# MB_RELAY.net
KiCad netlist of a schematic drawn in Altium Designer
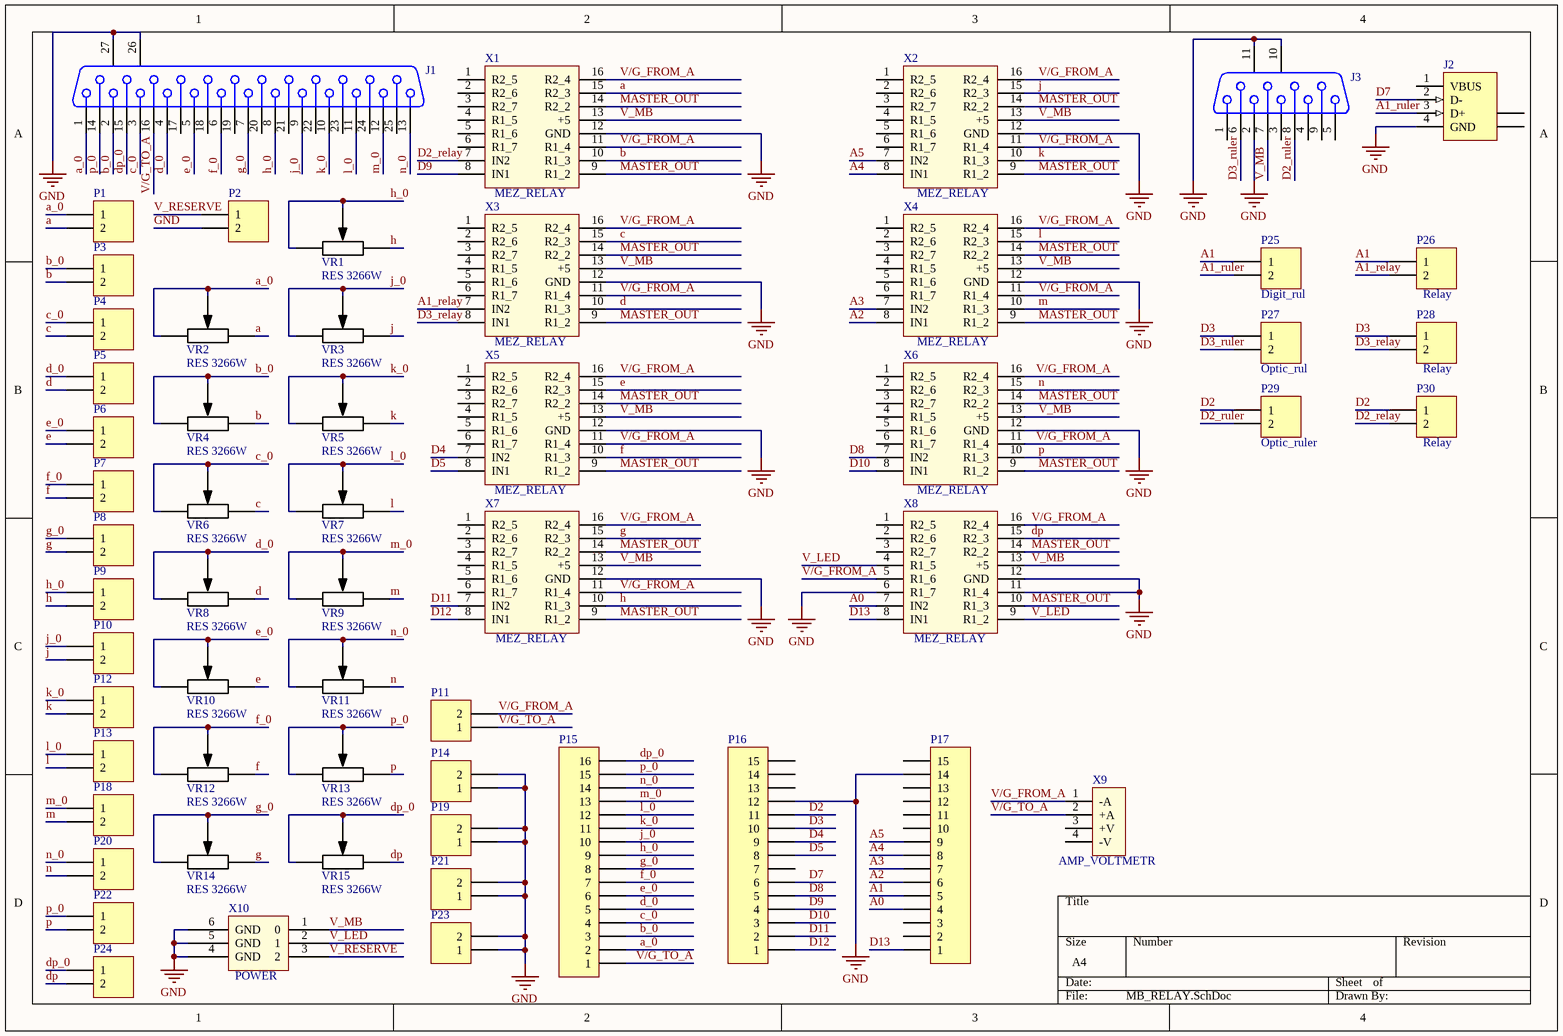
[diagram p0: MB_RELAY.SchDoc]

(export (version "E")
  (design (tool "Eeschema 10.0.6"))
  (components
    (comp (ref "J1")
      (value "D Connector 25")
      (footprint "DSUB1.385-2H25A")
      (description "Receptacle Assembly, 25 Position, Right Angle")
      (fields (field (name "PUBLISHER") "Altium Limited"))
      (libsource (lib "Miscellaneous Connectors") (part "D Connector 25"))
    )
    (comp (ref "J2")
      (value "1-353576-1")
      (footprint "353576")
      (description "USB 1.1, Right Angle, SMT, A Type, Receptacle, 4 Position, White")
      (fields (field (name "PUBLISHER") "Altium Limited"))
      (libsource (lib "AMP Serial Bus USB") (part "1-353576-1"))
    )
    (comp (ref "J3")
      (value "D Connector 9")
      (footprint "DSUB1.385-2H9")
      (description "Receptacle Assembly, 9 Position, Right Angle")
      (fields (field (name "PUBLISHER") "Altium Limited"))
      (libsource (lib "Miscellaneous Connectors") (part "D Connector 9"))
    )
    (comp (ref "P1")
      (value "Header 2")
      (footprint "HDR1X2")
      (description "Header, 2-Pin")
      (fields (field (name "PUBLISHER") "Altium Limited"))
      (libsource (lib "") (part "Header 2_1"))
    )
    (comp (ref "P2")
      (value "Header 2")
      (footprint "HDR1X2")
      (description "Header, 2-Pin")
      (fields (field (name "PUBLISHER") "Altium Limited"))
      (libsource (lib "") (part "Header 2_1"))
    )
    (comp (ref "P3")
      (value "Header 2")
      (footprint "HDR1X2")
      (description "Header, 2-Pin")
      (fields (field (name "PUBLISHER") "Altium Limited"))
      (libsource (lib "") (part "Header 2_1"))
    )
    (comp (ref "P4")
      (value "Header 2")
      (footprint "HDR1X2")
      (description "Header, 2-Pin")
      (fields (field (name "PUBLISHER") "Altium Limited"))
      (libsource (lib "") (part "Header 2_1"))
    )
    (comp (ref "P5")
      (value "Header 2")
      (footprint "HDR1X2")
      (description "Header, 2-Pin")
      (fields (field (name "PUBLISHER") "Altium Limited"))
      (libsource (lib "") (part "Header 2_1"))
    )
    (comp (ref "P6")
      (value "GND")
      (footprint "HDR1X2")
      (description "Header, 2-Pin")
      (fields (field (name "PUBLISHER") "Altium Limited"))
      (libsource (lib "") (part "Header 2_1"))
    )
    (comp (ref "P7")
      (value "GND")
      (footprint "HDR1X2")
      (description "Header, 2-Pin")
      (fields (field (name "PUBLISHER") "Altium Limited"))
      (libsource (lib "") (part "Header 2_1"))
    )
    (comp (ref "P8")
      (value "GND")
      (footprint "HDR1X2")
      (description "Header, 2-Pin")
      (fields (field (name "PUBLISHER") "Altium Limited"))
      (libsource (lib "") (part "Header 2_1"))
    )
    (comp (ref "P9")
      (value "GND")
      (footprint "HDR1X2")
      (description "Header, 2-Pin")
      (fields (field (name "PUBLISHER") "Altium Limited"))
      (libsource (lib "") (part "Header 2_1"))
    )
    (comp (ref "P10")
      (value "Header 2")
      (footprint "HDR1X2")
      (description "Header, 2-Pin")
      (fields (field (name "PUBLISHER") "Altium Limited"))
      (libsource (lib "") (part "Header 2_1"))
    )
    (comp (ref "P11")
      (value "Header 2")
      (footprint "HDR1X2")
      (description "Header, 2-Pin")
      (fields (field (name "PUBLISHER") "Altium Limited"))
      (libsource (lib "Miscellaneous Connectors") (part "Header 2"))
    )
    (comp (ref "P12")
      (value "Header 2")
      (footprint "HDR1X2")
      (description "Header, 2-Pin")
      (fields (field (name "PUBLISHER") "Altium Limited"))
      (libsource (lib "") (part "Header 2_1"))
    )
    (comp (ref "P13")
      (value "GND")
      (footprint "HDR1X2")
      (description "Header, 2-Pin")
      (fields (field (name "PUBLISHER") "Altium Limited"))
      (libsource (lib "") (part "Header 2_1"))
    )
    (comp (ref "P14")
      (value "GND")
      (footprint "HDR1X2")
      (description "Header, 2-Pin")
      (fields (field (name "PUBLISHER") "Altium Limited"))
      (libsource (lib "Miscellaneous Connectors") (part "Header 2"))
    )
    (comp (ref "P15")
      (value "Header 16")
      (footprint "HDR1X16")
      (description "Header, 16-Pin")
      (fields (field (name "PUBLISHER") "Altium Limited"))
      (libsource (lib "Miscellaneous Connectors") (part "Header 16"))
    )
    (comp (ref "P16")
      (value "Header 15")
      (footprint "HDR1X15")
      (description "Header, 15-Pin")
      (fields (field (name "PUBLISHER") "Altium Limited"))
      (libsource (lib "Miscellaneous Connectors") (part "Header 15"))
    )
    (comp (ref "P17")
      (value "Header 15")
      (footprint "HDR1X15")
      (description "Header, 15-Pin")
      (fields (field (name "PUBLISHER") "Altium Limited"))
      (libsource (lib "") (part "Header 15_1"))
    )
    (comp (ref "P18")
      (value "GND")
      (footprint "HDR1X2")
      (description "Header, 2-Pin")
      (fields (field (name "PUBLISHER") "Altium Limited"))
      (libsource (lib "") (part "Header 2_1"))
    )
    (comp (ref "P19")
      (value "GND")
      (footprint "HDR1X2")
      (description "Header, 2-Pin")
      (fields (field (name "PUBLISHER") "Altium Limited"))
      (libsource (lib "Miscellaneous Connectors") (part "Header 2"))
    )
    (comp (ref "P20")
      (value "GND")
      (footprint "HDR1X2")
      (description "Header, 2-Pin")
      (fields (field (name "PUBLISHER") "Altium Limited"))
      (libsource (lib "") (part "Header 2_1"))
    )
    (comp (ref "P21")
      (value "GND")
      (footprint "HDR1X2")
      (description "Header, 2-Pin")
      (fields (field (name "PUBLISHER") "Altium Limited"))
      (libsource (lib "Miscellaneous Connectors") (part "Header 2"))
    )
    (comp (ref "P22")
      (value "GND")
      (footprint "HDR1X2")
      (description "Header, 2-Pin")
      (fields (field (name "PUBLISHER") "Altium Limited"))
      (libsource (lib "") (part "Header 2_1"))
    )
    (comp (ref "P23")
      (value "GND")
      (footprint "HDR1X2")
      (description "Header, 2-Pin")
      (fields (field (name "PUBLISHER") "Altium Limited"))
      (libsource (lib "Miscellaneous Connectors") (part "Header 2"))
    )
    (comp (ref "P24")
      (value "GND")
      (footprint "HDR1X2")
      (description "Header, 2-Pin")
      (fields (field (name "PUBLISHER") "Altium Limited"))
      (libsource (lib "") (part "Header 2_1"))
    )
    (comp (ref "P25")
      (value "Digit_rul")
      (footprint "HDR1X2")
      (description "Header, 2-Pin")
      (fields (field (name "PUBLISHER") "Altium Limited"))
      (libsource (lib "") (part "Header 2_1"))
    )
    (comp (ref "P26")
      (value "Relay")
      (footprint "HDR1X2")
      (description "Header, 2-Pin")
      (fields (field (name "PUBLISHER") "Altium Limited"))
      (libsource (lib "") (part "Header 2_1"))
    )
    (comp (ref "P27")
      (value "Optic_rul")
      (footprint "HDR1X2")
      (description "Header, 2-Pin")
      (fields (field (name "PUBLISHER") "Altium Limited"))
      (libsource (lib "") (part "Header 2_1"))
    )
    (comp (ref "P28")
      (value "Relay")
      (footprint "HDR1X2")
      (description "Header, 2-Pin")
      (fields (field (name "PUBLISHER") "Altium Limited"))
      (libsource (lib "") (part "Header 2_1"))
    )
    (comp (ref "P29")
      (value "Optic_ruler")
      (footprint "HDR1X2")
      (description "Header, 2-Pin")
      (fields (field (name "PUBLISHER") "Altium Limited"))
      (libsource (lib "") (part "Header 2_1"))
    )
    (comp (ref "P30")
      (value "Relay")
      (footprint "HDR1X2")
      (description "Header, 2-Pin")
      (fields (field (name "PUBLISHER") "Altium Limited"))
      (libsource (lib "") (part "Header 2_1"))
    )
    (comp (ref "VR1")
      (value "RES 3266W")
      (footprint "aab_Passive:RES 3266W")
      (libsource (lib "aab_Schlib") (part "RES 3266W"))
    )
    (comp (ref "VR2")
      (value "RES 3266W")
      (footprint "aab_Passive:RES 3266W")
      (libsource (lib "aab_Schlib") (part "RES 3266W"))
    )
    (comp (ref "VR3")
      (value "RES 3266W")
      (footprint "aab_Passive:RES 3266W")
      (libsource (lib "aab_Schlib") (part "RES 3266W"))
    )
    (comp (ref "VR4")
      (value "RES 3266W")
      (footprint "aab_Passive:RES 3266W")
      (libsource (lib "aab_Schlib") (part "RES 3266W"))
    )
    (comp (ref "VR5")
      (value "RES 3266W")
      (footprint "aab_Passive:RES 3266W")
      (libsource (lib "aab_Schlib") (part "RES 3266W"))
    )
    (comp (ref "VR6")
      (value "RES 3266W")
      (footprint "aab_Passive:RES 3266W")
      (libsource (lib "aab_Schlib") (part "RES 3266W"))
    )
    (comp (ref "VR7")
      (value "RES 3266W")
      (footprint "aab_Passive:RES 3266W")
      (libsource (lib "aab_Schlib") (part "RES 3266W"))
    )
    (comp (ref "VR8")
      (value "RES 3266W")
      (footprint "aab_Passive:RES 3266W")
      (libsource (lib "aab_Schlib") (part "RES 3266W"))
    )
    (comp (ref "VR9")
      (value "RES 3266W")
      (footprint "aab_Passive:RES 3266W")
      (libsource (lib "aab_Schlib") (part "RES 3266W"))
    )
    (comp (ref "VR10")
      (value "RES 3266W")
      (footprint "aab_Passive:RES 3266W")
      (libsource (lib "aab_Schlib") (part "RES 3266W"))
    )
    (comp (ref "VR11")
      (value "RES 3266W")
      (footprint "aab_Passive:RES 3266W")
      (libsource (lib "aab_Schlib") (part "RES 3266W"))
    )
    (comp (ref "VR12")
      (value "RES 3266W")
      (footprint "aab_Passive:RES 3266W")
      (libsource (lib "aab_Schlib") (part "RES 3266W"))
    )
    (comp (ref "VR13")
      (value "RES 3266W")
      (footprint "aab_Passive:RES 3266W")
      (libsource (lib "aab_Schlib") (part "RES 3266W"))
    )
    (comp (ref "VR14")
      (value "RES 3266W")
      (footprint "aab_Passive:RES 3266W")
      (libsource (lib "aab_Schlib") (part "RES 3266W"))
    )
    (comp (ref "VR15")
      (value "RES 3266W")
      (footprint "aab_Passive:RES 3266W")
      (libsource (lib "aab_Schlib") (part "RES 3266W"))
    )
    (comp (ref "X1")
      (value "MEZ_RELAY")
      (footprint "MEZ_RELAY")
      (libsource (lib "msp_SchLib") (part "MEZ_RELAY"))
    )
    (comp (ref "X2")
      (value "MEZ_RELAY")
      (footprint "MEZ_RELAY")
      (libsource (lib "msp_SchLib") (part "MEZ_RELAY"))
    )
    (comp (ref "X3")
      (value "MEZ_RELAY")
      (footprint "MEZ_RELAY")
      (libsource (lib "msp_SchLib") (part "MEZ_RELAY"))
    )
    (comp (ref "X4")
      (value "MEZ_RELAY")
      (footprint "MEZ_RELAY")
      (libsource (lib "msp_SchLib") (part "MEZ_RELAY"))
    )
    (comp (ref "X5")
      (value "MEZ_RELAY")
      (footprint "MEZ_RELAY")
      (libsource (lib "msp_SchLib") (part "MEZ_RELAY"))
    )
    (comp (ref "X6")
      (value "MEZ_RELAY")
      (footprint "MEZ_RELAY")
      (libsource (lib "msp_SchLib") (part "MEZ_RELAY"))
    )
    (comp (ref "X7")
      (value "MEZ_RELAY")
      (footprint "MEZ_RELAY")
      (libsource (lib "msp_SchLib") (part "MEZ_RELAY"))
    )
    (comp (ref "X8")
      (value "MEZ_RELAY")
      (footprint "MEZ_RELAY")
      (libsource (lib "msp_SchLib") (part "MEZ_RELAY"))
    )
    (comp (ref "X9")
      (value "AMP_VOLTMETR")
      (footprint "vpl_Passive:AMP_VOLTMETER")
      (libsource (lib "msp_SchLib") (part "AMP_VOLTMETR"))
    )
    (comp (ref "X10")
      (value "POWER")
      (footprint "vpl_Passive:POWER")
      (libsource (lib "msp_SchLib") (part "POWER"))
    )
  )
  (nets
    (net (code "1") (name "/A0") (class "Default")
      (node (ref "P17") (pin "4") (pinfunction "4_4") (pintype "passive"))
      (node (ref "X8") (pin "7") (pinfunction "IN2_7") (pintype "passive"))
    )
    (net (code "2") (name "/A1") (class "Default")
      (node (ref "P17") (pin "5") (pinfunction "5_5") (pintype "passive"))
      (node (ref "P25") (pin "1") (pinfunction "1_1") (pintype "passive"))
      (node (ref "P26") (pin "1") (pinfunction "1_1") (pintype "passive"))
    )
    (net (code "3") (name "/A1_relay") (class "Default")
      (node (ref "P26") (pin "2") (pinfunction "2_2") (pintype "passive"))
      (node (ref "X3") (pin "7") (pinfunction "IN2_7") (pintype "passive"))
    )
    (net (code "4") (name "/A1_ruler") (class "Default")
      (node (ref "J2") (pin "3") (pinfunction "D+_3") (pintype "input"))
      (node (ref "P25") (pin "2") (pinfunction "2_2") (pintype "passive"))
    )
    (net (code "5") (name "/A2") (class "Default")
      (node (ref "P17") (pin "6") (pinfunction "6_6") (pintype "passive"))
      (node (ref "X4") (pin "8") (pinfunction "IN1_8") (pintype "passive"))
    )
    (net (code "6") (name "/A3") (class "Default")
      (node (ref "P17") (pin "7") (pinfunction "7_7") (pintype "passive"))
      (node (ref "X4") (pin "7") (pinfunction "IN2_7") (pintype "passive"))
    )
    (net (code "7") (name "/A4") (class "Default")
      (node (ref "P17") (pin "8") (pinfunction "8_8") (pintype "passive"))
      (node (ref "X2") (pin "8") (pinfunction "IN1_8") (pintype "passive"))
    )
    (net (code "8") (name "/A5") (class "Default")
      (node (ref "P17") (pin "9") (pinfunction "9_9") (pintype "passive"))
      (node (ref "X2") (pin "7") (pinfunction "IN2_7") (pintype "passive"))
    )
    (net (code "9") (name "/D2") (class "Default")
      (node (ref "P16") (pin "11") (pinfunction "11_11") (pintype "passive"))
      (node (ref "P29") (pin "1") (pinfunction "1_1") (pintype "passive"))
      (node (ref "P30") (pin "1") (pinfunction "1_1") (pintype "passive"))
    )
    (net (code "10") (name "/D2_relay") (class "Default")
      (node (ref "P30") (pin "2") (pinfunction "2_2") (pintype "passive"))
      (node (ref "X1") (pin "7") (pinfunction "IN2_7") (pintype "passive"))
    )
    (net (code "11") (name "/D2_ruler") (class "Default")
      (node (ref "J3") (pin "8") (pinfunction "8_8") (pintype "passive"))
      (node (ref "P29") (pin "2") (pinfunction "2_2") (pintype "passive"))
    )
    (net (code "12") (name "/D3") (class "Default")
      (node (ref "P16") (pin "10") (pinfunction "10_10") (pintype "passive"))
      (node (ref "P27") (pin "1") (pinfunction "1_1") (pintype "passive"))
      (node (ref "P28") (pin "1") (pinfunction "1_1") (pintype "passive"))
    )
    (net (code "13") (name "/D3_relay") (class "Default")
      (node (ref "P28") (pin "2") (pinfunction "2_2") (pintype "passive"))
      (node (ref "X3") (pin "8") (pinfunction "IN1_8") (pintype "passive"))
    )
    (net (code "14") (name "/D3_ruler") (class "Default")
      (node (ref "J3") (pin "6") (pinfunction "6_6") (pintype "passive"))
      (node (ref "P27") (pin "2") (pinfunction "2_2") (pintype "passive"))
    )
    (net (code "15") (name "/D4") (class "Default")
      (node (ref "P16") (pin "9") (pinfunction "9_9") (pintype "passive"))
      (node (ref "X5") (pin "7") (pinfunction "IN2_7") (pintype "passive"))
    )
    (net (code "16") (name "/D5") (class "Default")
      (node (ref "P16") (pin "8") (pinfunction "8_8") (pintype "passive"))
      (node (ref "X5") (pin "8") (pinfunction "IN1_8") (pintype "passive"))
    )
    (net (code "17") (name "/D7") (class "Default")
      (node (ref "J2") (pin "2") (pinfunction "D-_2") (pintype "input"))
      (node (ref "P16") (pin "6") (pinfunction "6_6") (pintype "passive"))
    )
    (net (code "18") (name "/D8") (class "Default")
      (node (ref "P16") (pin "5") (pinfunction "5_5") (pintype "passive"))
      (node (ref "X6") (pin "7") (pinfunction "IN2_7") (pintype "passive"))
    )
    (net (code "19") (name "/D9") (class "Default")
      (node (ref "P16") (pin "4") (pinfunction "4_4") (pintype "passive"))
      (node (ref "X1") (pin "8") (pinfunction "IN1_8") (pintype "passive"))
    )
    (net (code "20") (name "/D10") (class "Default")
      (node (ref "P16") (pin "3") (pinfunction "3_3") (pintype "passive"))
      (node (ref "X6") (pin "8") (pinfunction "IN1_8") (pintype "passive"))
    )
    (net (code "21") (name "/D11") (class "Default")
      (node (ref "P16") (pin "2") (pinfunction "2_2") (pintype "passive"))
      (node (ref "X7") (pin "7") (pinfunction "IN2_7") (pintype "passive"))
    )
    (net (code "22") (name "/D12") (class "Default")
      (node (ref "P16") (pin "1") (pinfunction "1_1") (pintype "passive"))
      (node (ref "X7") (pin "8") (pinfunction "IN1_8") (pintype "passive"))
    )
    (net (code "23") (name "/D13") (class "Default")
      (node (ref "P17") (pin "1") (pinfunction "1_1") (pintype "passive"))
      (node (ref "X8") (pin "8") (pinfunction "IN1_8") (pintype "passive"))
    )
    (net (code "24") (name "/MASTER_OUT") (class "Default")
      (node (ref "X1") (pin "14") (pinfunction "R2_2_14") (pintype "passive"))
      (node (ref "X1") (pin "9") (pinfunction "R1_2_9") (pintype "passive"))
      (node (ref "X2") (pin "14") (pinfunction "R2_2_14") (pintype "passive"))
      (node (ref "X2") (pin "9") (pinfunction "R1_2_9") (pintype "passive"))
      (node (ref "X3") (pin "14") (pinfunction "R2_2_14") (pintype "passive"))
      (node (ref "X3") (pin "9") (pinfunction "R1_2_9") (pintype "passive"))
      (node (ref "X4") (pin "14") (pinfunction "R2_2_14") (pintype "passive"))
      (node (ref "X4") (pin "9") (pinfunction "R1_2_9") (pintype "passive"))
      (node (ref "X5") (pin "14") (pinfunction "R2_2_14") (pintype "passive"))
      (node (ref "X5") (pin "9") (pinfunction "R1_2_9") (pintype "passive"))
      (node (ref "X6") (pin "14") (pinfunction "R2_2_14") (pintype "passive"))
      (node (ref "X6") (pin "9") (pinfunction "R1_2_9") (pintype "passive"))
      (node (ref "X7") (pin "14") (pinfunction "R2_2_14") (pintype "passive"))
      (node (ref "X7") (pin "9") (pinfunction "R1_2_9") (pintype "passive"))
      (node (ref "X8") (pin "10") (pinfunction "R1_3_10") (pintype "passive"))
      (node (ref "X8") (pin "14") (pinfunction "R2_2_14") (pintype "passive"))
    )
    (net (code "25") (name "/V_LED") (class "Default")
      (node (ref "X10") (pin "2") (pinfunction "1_2") (pintype "passive"))
      (node (ref "X8") (pin "4") (pinfunction "R1_5_4") (pintype "passive"))
      (node (ref "X8") (pin "9") (pinfunction "R1_2_9") (pintype "passive"))
    )
    (net (code "26") (name "/V_MB") (class "Default")
      (node (ref "J3") (pin "7") (pinfunction "7_7") (pintype "passive"))
      (node (ref "X1") (pin "13") (pinfunction "+5_13") (pintype "passive"))
      (node (ref "X10") (pin "1") (pinfunction "0_1") (pintype "passive"))
      (node (ref "X2") (pin "13") (pinfunction "+5_13") (pintype "passive"))
      (node (ref "X3") (pin "13") (pinfunction "+5_13") (pintype "passive"))
      (node (ref "X4") (pin "13") (pinfunction "+5_13") (pintype "passive"))
      (node (ref "X5") (pin "13") (pinfunction "+5_13") (pintype "passive"))
      (node (ref "X6") (pin "13") (pinfunction "+5_13") (pintype "passive"))
      (node (ref "X7") (pin "13") (pinfunction "+5_13") (pintype "passive"))
      (node (ref "X8") (pin "13") (pinfunction "+5_13") (pintype "passive"))
    )
    (net (code "27") (name "/V_RESERVE") (class "Default")
      (node (ref "P2") (pin "1") (pinfunction "1_1") (pintype "passive"))
      (node (ref "X10") (pin "3") (pinfunction "2_3") (pintype "passive"))
    )
    (net (code "28") (name "/V{slash}G_FROM_A") (class "Default")
      (node (ref "P11") (pin "2") (pinfunction "2_2") (pintype "passive"))
      (node (ref "X1") (pin "11") (pinfunction "R1_4_11") (pintype "passive"))
      (node (ref "X1") (pin "16") (pinfunction "R2_4_16") (pintype "passive"))
      (node (ref "X2") (pin "11") (pinfunction "R1_4_11") (pintype "passive"))
      (node (ref "X2") (pin "16") (pinfunction "R2_4_16") (pintype "passive"))
      (node (ref "X3") (pin "11") (pinfunction "R1_4_11") (pintype "passive"))
      (node (ref "X3") (pin "16") (pinfunction "R2_4_16") (pintype "passive"))
      (node (ref "X4") (pin "11") (pinfunction "R1_4_11") (pintype "passive"))
      (node (ref "X4") (pin "16") (pinfunction "R2_4_16") (pintype "passive"))
      (node (ref "X5") (pin "11") (pinfunction "R1_4_11") (pintype "passive"))
      (node (ref "X5") (pin "16") (pinfunction "R2_4_16") (pintype "passive"))
      (node (ref "X6") (pin "11") (pinfunction "R1_4_11") (pintype "passive"))
      (node (ref "X6") (pin "16") (pinfunction "R2_4_16") (pintype "passive"))
      (node (ref "X7") (pin "11") (pinfunction "R1_4_11") (pintype "passive"))
      (node (ref "X7") (pin "16") (pinfunction "R2_4_16") (pintype "passive"))
      (node (ref "X8") (pin "16") (pinfunction "R2_4_16") (pintype "passive"))
      (node (ref "X8") (pin "5") (pinfunction "R1_6_5") (pintype "passive"))
      (node (ref "X9") (pin "1") (pinfunction "-A_1") (pintype "passive"))
    )
    (net (code "29") (name "/V{slash}G_TO_A") (class "Default")
      (node (ref "J1") (pin "16") (pinfunction "16_16") (pintype "passive"))
      (node (ref "P11") (pin "1") (pinfunction "1_1") (pintype "passive"))
      (node (ref "P15") (pin "1") (pinfunction "1_1") (pintype "passive"))
      (node (ref "X9") (pin "2") (pinfunction "+A_2") (pintype "passive"))
    )
    (net (code "30") (name "/a") (class "Default")
      (node (ref "P1") (pin "2") (pinfunction "2_2") (pintype "passive"))
      (node (ref "VR2") (pin "3") (pinfunction "3_3") (pintype "passive"))
      (node (ref "X1") (pin "15") (pinfunction "R2_3_15") (pintype "passive"))
    )
    (net (code "31") (name "/a_0") (class "Default")
      (node (ref "J1") (pin "1") (pinfunction "1_1") (pintype "passive"))
      (node (ref "P1") (pin "1") (pinfunction "1_1") (pintype "passive"))
      (node (ref "P15") (pin "2") (pinfunction "2_2") (pintype "passive"))
      (node (ref "VR2") (pin "1") (pinfunction "1_1") (pintype "passive"))
      (node (ref "VR2") (pin "2") (pinfunction "2_2") (pintype "passive"))
    )
    (net (code "32") (name "/b") (class "Default")
      (node (ref "P3") (pin "2") (pinfunction "2_2") (pintype "passive"))
      (node (ref "VR4") (pin "3") (pinfunction "3_3") (pintype "passive"))
      (node (ref "X1") (pin "10") (pinfunction "R1_3_10") (pintype "passive"))
    )
    (net (code "33") (name "/b_0") (class "Default")
      (node (ref "J1") (pin "2") (pinfunction "2_2") (pintype "passive"))
      (node (ref "P15") (pin "3") (pinfunction "3_3") (pintype "passive"))
      (node (ref "P3") (pin "1") (pinfunction "1_1") (pintype "passive"))
      (node (ref "VR4") (pin "1") (pinfunction "1_1") (pintype "passive"))
      (node (ref "VR4") (pin "2") (pinfunction "2_2") (pintype "passive"))
    )
    (net (code "34") (name "/c") (class "Default")
      (node (ref "P4") (pin "2") (pinfunction "2_2") (pintype "passive"))
      (node (ref "VR6") (pin "3") (pinfunction "3_3") (pintype "passive"))
      (node (ref "X3") (pin "15") (pinfunction "R2_3_15") (pintype "passive"))
    )
    (net (code "35") (name "/c_0") (class "Default")
      (node (ref "J1") (pin "3") (pinfunction "3_3") (pintype "passive"))
      (node (ref "P15") (pin "4") (pinfunction "4_4") (pintype "passive"))
      (node (ref "P4") (pin "1") (pinfunction "1_1") (pintype "passive"))
      (node (ref "VR6") (pin "1") (pinfunction "1_1") (pintype "passive"))
      (node (ref "VR6") (pin "2") (pinfunction "2_2") (pintype "passive"))
    )
    (net (code "36") (name "/d") (class "Default")
      (node (ref "P5") (pin "2") (pinfunction "2_2") (pintype "passive"))
      (node (ref "VR8") (pin "3") (pinfunction "3_3") (pintype "passive"))
      (node (ref "X3") (pin "10") (pinfunction "R1_3_10") (pintype "passive"))
    )
    (net (code "37") (name "/d_0") (class "Default")
      (node (ref "J1") (pin "4") (pinfunction "4_4") (pintype "passive"))
      (node (ref "P15") (pin "5") (pinfunction "5_5") (pintype "passive"))
      (node (ref "P5") (pin "1") (pinfunction "1_1") (pintype "passive"))
      (node (ref "VR8") (pin "1") (pinfunction "1_1") (pintype "passive"))
      (node (ref "VR8") (pin "2") (pinfunction "2_2") (pintype "passive"))
    )
    (net (code "38") (name "/dp") (class "Default")
      (node (ref "P24") (pin "2") (pinfunction "2_2") (pintype "passive"))
      (node (ref "VR15") (pin "3") (pinfunction "3_3") (pintype "passive"))
      (node (ref "X8") (pin "15") (pinfunction "R2_3_15") (pintype "passive"))
    )
    (net (code "39") (name "/dp_0") (class "Default")
      (node (ref "J1") (pin "15") (pinfunction "15_15") (pintype "passive"))
      (node (ref "P15") (pin "16") (pinfunction "16_16") (pintype "passive"))
      (node (ref "P24") (pin "1") (pinfunction "1_1") (pintype "passive"))
      (node (ref "VR15") (pin "1") (pinfunction "1_1") (pintype "passive"))
      (node (ref "VR15") (pin "2") (pinfunction "2_2") (pintype "passive"))
    )
    (net (code "40") (name "/e") (class "Default")
      (node (ref "P6") (pin "2") (pinfunction "2_2") (pintype "passive"))
      (node (ref "VR10") (pin "3") (pinfunction "3_3") (pintype "passive"))
      (node (ref "X5") (pin "15") (pinfunction "R2_3_15") (pintype "passive"))
    )
    (net (code "41") (name "/e_0") (class "Default")
      (node (ref "J1") (pin "5") (pinfunction "5_5") (pintype "passive"))
      (node (ref "P15") (pin "6") (pinfunction "6_6") (pintype "passive"))
      (node (ref "P6") (pin "1") (pinfunction "1_1") (pintype "passive"))
      (node (ref "VR10") (pin "1") (pinfunction "1_1") (pintype "passive"))
      (node (ref "VR10") (pin "2") (pinfunction "2_2") (pintype "passive"))
    )
    (net (code "42") (name "/f") (class "Default")
      (node (ref "P7") (pin "2") (pinfunction "2_2") (pintype "passive"))
      (node (ref "VR12") (pin "3") (pinfunction "3_3") (pintype "passive"))
      (node (ref "X5") (pin "10") (pinfunction "R1_3_10") (pintype "passive"))
    )
    (net (code "43") (name "/f_0") (class "Default")
      (node (ref "J1") (pin "6") (pinfunction "6_6") (pintype "passive"))
      (node (ref "P15") (pin "7") (pinfunction "7_7") (pintype "passive"))
      (node (ref "P7") (pin "1") (pinfunction "1_1") (pintype "passive"))
      (node (ref "VR12") (pin "1") (pinfunction "1_1") (pintype "passive"))
      (node (ref "VR12") (pin "2") (pinfunction "2_2") (pintype "passive"))
    )
    (net (code "44") (name "/g") (class "Default")
      (node (ref "P8") (pin "2") (pinfunction "2_2") (pintype "passive"))
      (node (ref "VR14") (pin "3") (pinfunction "3_3") (pintype "passive"))
      (node (ref "X7") (pin "15") (pinfunction "R2_3_15") (pintype "passive"))
    )
    (net (code "45") (name "/g_0") (class "Default")
      (node (ref "J1") (pin "7") (pinfunction "7_7") (pintype "passive"))
      (node (ref "P15") (pin "8") (pinfunction "8_8") (pintype "passive"))
      (node (ref "P8") (pin "1") (pinfunction "1_1") (pintype "passive"))
      (node (ref "VR14") (pin "1") (pinfunction "1_1") (pintype "passive"))
      (node (ref "VR14") (pin "2") (pinfunction "2_2") (pintype "passive"))
    )
    (net (code "46") (name "/h") (class "Default")
      (node (ref "P9") (pin "2") (pinfunction "2_2") (pintype "passive"))
      (node (ref "VR1") (pin "3") (pinfunction "3_3") (pintype "passive"))
      (node (ref "X7") (pin "10") (pinfunction "R1_3_10") (pintype "passive"))
    )
    (net (code "47") (name "/h_0") (class "Default")
      (node (ref "J1") (pin "8") (pinfunction "8_8") (pintype "passive"))
      (node (ref "P15") (pin "9") (pinfunction "9_9") (pintype "passive"))
      (node (ref "P9") (pin "1") (pinfunction "1_1") (pintype "passive"))
      (node (ref "VR1") (pin "1") (pinfunction "1_1") (pintype "passive"))
      (node (ref "VR1") (pin "2") (pinfunction "2_2") (pintype "passive"))
    )
    (net (code "48") (name "/j") (class "Default")
      (node (ref "P10") (pin "2") (pinfunction "2_2") (pintype "passive"))
      (node (ref "VR3") (pin "3") (pinfunction "3_3") (pintype "passive"))
      (node (ref "X2") (pin "15") (pinfunction "R2_3_15") (pintype "passive"))
    )
    (net (code "49") (name "/j_0") (class "Default")
      (node (ref "J1") (pin "9") (pinfunction "9_9") (pintype "passive"))
      (node (ref "P10") (pin "1") (pinfunction "1_1") (pintype "passive"))
      (node (ref "P15") (pin "10") (pinfunction "10_10") (pintype "passive"))
      (node (ref "VR3") (pin "1") (pinfunction "1_1") (pintype "passive"))
      (node (ref "VR3") (pin "2") (pinfunction "2_2") (pintype "passive"))
    )
    (net (code "50") (name "/k") (class "Default")
      (node (ref "P12") (pin "2") (pinfunction "2_2") (pintype "passive"))
      (node (ref "VR5") (pin "3") (pinfunction "3_3") (pintype "passive"))
      (node (ref "X2") (pin "10") (pinfunction "R1_3_10") (pintype "passive"))
    )
    (net (code "51") (name "/k_0") (class "Default")
      (node (ref "J1") (pin "10") (pinfunction "10_10") (pintype "passive"))
      (node (ref "P12") (pin "1") (pinfunction "1_1") (pintype "passive"))
      (node (ref "P15") (pin "11") (pinfunction "11_11") (pintype "passive"))
      (node (ref "VR5") (pin "1") (pinfunction "1_1") (pintype "passive"))
      (node (ref "VR5") (pin "2") (pinfunction "2_2") (pintype "passive"))
    )
    (net (code "52") (name "/l") (class "Default")
      (node (ref "P13") (pin "2") (pinfunction "2_2") (pintype "passive"))
      (node (ref "VR7") (pin "3") (pinfunction "3_3") (pintype "passive"))
      (node (ref "X4") (pin "15") (pinfunction "R2_3_15") (pintype "passive"))
    )
    (net (code "53") (name "/l_0") (class "Default")
      (node (ref "J1") (pin "11") (pinfunction "11_11") (pintype "passive"))
      (node (ref "P13") (pin "1") (pinfunction "1_1") (pintype "passive"))
      (node (ref "P15") (pin "12") (pinfunction "12_12") (pintype "passive"))
      (node (ref "VR7") (pin "1") (pinfunction "1_1") (pintype "passive"))
      (node (ref "VR7") (pin "2") (pinfunction "2_2") (pintype "passive"))
    )
    (net (code "54") (name "/m") (class "Default")
      (node (ref "P18") (pin "2") (pinfunction "2_2") (pintype "passive"))
      (node (ref "VR9") (pin "3") (pinfunction "3_3") (pintype "passive"))
      (node (ref "X4") (pin "10") (pinfunction "R1_3_10") (pintype "passive"))
    )
    (net (code "55") (name "/m_0") (class "Default")
      (node (ref "J1") (pin "12") (pinfunction "12_12") (pintype "passive"))
      (node (ref "P15") (pin "13") (pinfunction "13_13") (pintype "passive"))
      (node (ref "P18") (pin "1") (pinfunction "1_1") (pintype "passive"))
      (node (ref "VR9") (pin "1") (pinfunction "1_1") (pintype "passive"))
      (node (ref "VR9") (pin "2") (pinfunction "2_2") (pintype "passive"))
    )
    (net (code "56") (name "/n") (class "Default")
      (node (ref "P20") (pin "2") (pinfunction "2_2") (pintype "passive"))
      (node (ref "VR11") (pin "3") (pinfunction "3_3") (pintype "passive"))
      (node (ref "X6") (pin "15") (pinfunction "R2_3_15") (pintype "passive"))
    )
    (net (code "57") (name "/n_0") (class "Default")
      (node (ref "J1") (pin "13") (pinfunction "13_13") (pintype "passive"))
      (node (ref "P15") (pin "14") (pinfunction "14_14") (pintype "passive"))
      (node (ref "P20") (pin "1") (pinfunction "1_1") (pintype "passive"))
      (node (ref "VR11") (pin "1") (pinfunction "1_1") (pintype "passive"))
      (node (ref "VR11") (pin "2") (pinfunction "2_2") (pintype "passive"))
    )
    (net (code "58") (name "/p") (class "Default")
      (node (ref "P22") (pin "2") (pinfunction "2_2") (pintype "passive"))
      (node (ref "VR13") (pin "3") (pinfunction "3_3") (pintype "passive"))
      (node (ref "X6") (pin "10") (pinfunction "R1_3_10") (pintype "passive"))
    )
    (net (code "59") (name "/p_0") (class "Default")
      (node (ref "J1") (pin "14") (pinfunction "14_14") (pintype "passive"))
      (node (ref "P15") (pin "15") (pinfunction "15_15") (pintype "passive"))
      (node (ref "P22") (pin "1") (pinfunction "1_1") (pintype "passive"))
      (node (ref "VR13") (pin "1") (pinfunction "1_1") (pintype "passive"))
      (node (ref "VR13") (pin "2") (pinfunction "2_2") (pintype "passive"))
    )
    (net (code "60") (name "GND") (class "Default")
      (node (ref "J1") (pin "26") (pinfunction "MH1_26") (pintype "passive"))
      (node (ref "J1") (pin "27") (pinfunction "MH2_27") (pintype "passive"))
      (node (ref "J2") (pin "4") (pinfunction "GND_4") (pintype "power_in"))
      (node (ref "J3") (pin "10") (pinfunction "MH1_10") (pintype "passive"))
      (node (ref "J3") (pin "11") (pinfunction "MH2_11") (pintype "passive"))
      (node (ref "J3") (pin "2") (pinfunction "2_2") (pintype "passive"))
      (node (ref "P14") (pin "1") (pinfunction "1_1") (pintype "passive"))
      (node (ref "P14") (pin "2") (pinfunction "2_2") (pintype "passive"))
      (node (ref "P16") (pin "12") (pinfunction "12_12") (pintype "passive"))
      (node (ref "P17") (pin "14") (pinfunction "14_14") (pintype "passive"))
      (node (ref "P19") (pin "1") (pinfunction "1_1") (pintype "passive"))
      (node (ref "P19") (pin "2") (pinfunction "2_2") (pintype "passive"))
      (node (ref "P2") (pin "2") (pinfunction "2_2") (pintype "passive"))
      (node (ref "P21") (pin "1") (pinfunction "1_1") (pintype "passive"))
      (node (ref "P21") (pin "2") (pinfunction "2_2") (pintype "passive"))
      (node (ref "P23") (pin "1") (pinfunction "1_1") (pintype "passive"))
      (node (ref "P23") (pin "2") (pinfunction "2_2") (pintype "passive"))
      (node (ref "X1") (pin "12") (pinfunction "GND_12") (pintype "passive"))
      (node (ref "X10") (pin "4") (pinfunction "GND_4") (pintype "passive"))
      (node (ref "X10") (pin "5") (pinfunction "GND_5") (pintype "passive"))
      (node (ref "X10") (pin "6") (pinfunction "GND_6") (pintype "passive"))
      (node (ref "X2") (pin "12") (pinfunction "GND_12") (pintype "passive"))
      (node (ref "X3") (pin "12") (pinfunction "GND_12") (pintype "passive"))
      (node (ref "X4") (pin "12") (pinfunction "GND_12") (pintype "passive"))
      (node (ref "X5") (pin "12") (pinfunction "GND_12") (pintype "passive"))
      (node (ref "X6") (pin "12") (pinfunction "GND_12") (pintype "passive"))
      (node (ref "X7") (pin "12") (pinfunction "GND_12") (pintype "passive"))
      (node (ref "X8") (pin "11") (pinfunction "R1_4_11") (pintype "passive"))
      (node (ref "X8") (pin "12") (pinfunction "GND_12") (pintype "passive"))
      (node (ref "X8") (pin "6") (pinfunction "R1_7_6") (pintype "passive"))
    )
    (net (code "61") (name "unconnected-(J1-Pad17)") (class "Default")
      (node (ref "J1") (pin "17") (pinfunction "17_17") (pintype "passive"))
    )
    (net (code "62") (name "unconnected-(J1-Pad18)") (class "Default")
      (node (ref "J1") (pin "18") (pinfunction "18_18") (pintype "passive"))
    )
    (net (code "63") (name "unconnected-(J1-Pad19)") (class "Default")
      (node (ref "J1") (pin "19") (pinfunction "19_19") (pintype "passive"))
    )
    (net (code "64") (name "unconnected-(J1-Pad20)") (class "Default")
      (node (ref "J1") (pin "20") (pinfunction "20_20") (pintype "passive"))
    )
    (net (code "65") (name "unconnected-(J1-Pad21)") (class "Default")
      (node (ref "J1") (pin "21") (pinfunction "21_21") (pintype "passive"))
    )
    (net (code "66") (name "unconnected-(J1-Pad22)") (class "Default")
      (node (ref "J1") (pin "22") (pinfunction "22_22") (pintype "passive"))
    )
    (net (code "67") (name "unconnected-(J1-Pad23)") (class "Default")
      (node (ref "J1") (pin "23") (pinfunction "23_23") (pintype "passive"))
    )
    (net (code "68") (name "unconnected-(J1-Pad24)") (class "Default")
      (node (ref "J1") (pin "24") (pinfunction "24_24") (pintype "passive"))
    )
    (net (code "69") (name "unconnected-(J1-Pad25)") (class "Default")
      (node (ref "J1") (pin "25") (pinfunction "25_25") (pintype "passive"))
    )
    (net (code "70") (name "unconnected-(J2-SHLD-Pad5)") (class "Default")
      (node (ref "J2") (pin "5") (pinfunction "SHLD_5") (pintype "passive"))
    )
    (net (code "71") (name "unconnected-(J2-SHLD-Pad6)") (class "Default")
      (node (ref "J2") (pin "6") (pinfunction "SHLD_6") (pintype "passive"))
    )
    (net (code "72") (name "unconnected-(J2-VBUS-Pad1)") (class "Default")
      (node (ref "J2") (pin "1") (pinfunction "VBUS_1") (pintype "power_in"))
    )
    (net (code "73") (name "unconnected-(J3-Pad1)") (class "Default")
      (node (ref "J3") (pin "1") (pinfunction "1_1") (pintype "passive"))
    )
    (net (code "74") (name "unconnected-(J3-Pad3)") (class "Default")
      (node (ref "J3") (pin "3") (pinfunction "3_3") (pintype "passive"))
    )
    (net (code "75") (name "unconnected-(J3-Pad4)") (class "Default")
      (node (ref "J3") (pin "4") (pinfunction "4_4") (pintype "passive"))
    )
    (net (code "76") (name "unconnected-(J3-Pad5)") (class "Default")
      (node (ref "J3") (pin "5") (pinfunction "5_5") (pintype "passive"))
    )
    (net (code "77") (name "unconnected-(J3-Pad9)") (class "Default")
      (node (ref "J3") (pin "9") (pinfunction "9_9") (pintype "passive"))
    )
    (net (code "78") (name "unconnected-(P16-Pad7)") (class "Default")
      (node (ref "P16") (pin "7") (pinfunction "7_7") (pintype "passive"))
    )
    (net (code "79") (name "unconnected-(P16-Pad13)") (class "Default")
      (node (ref "P16") (pin "13") (pinfunction "13_13") (pintype "passive"))
    )
    (net (code "80") (name "unconnected-(P16-Pad14)") (class "Default")
      (node (ref "P16") (pin "14") (pinfunction "14_14") (pintype "passive"))
    )
    (net (code "81") (name "unconnected-(P16-Pad15)") (class "Default")
      (node (ref "P16") (pin "15") (pinfunction "15_15") (pintype "passive"))
    )
    (net (code "82") (name "unconnected-(P17-Pad2)") (class "Default")
      (node (ref "P17") (pin "2") (pinfunction "2_2") (pintype "passive"))
    )
    (net (code "83") (name "unconnected-(P17-Pad3)") (class "Default")
      (node (ref "P17") (pin "3") (pinfunction "3_3") (pintype "passive"))
    )
    (net (code "84") (name "unconnected-(P17-Pad10)") (class "Default")
      (node (ref "P17") (pin "10") (pinfunction "10_10") (pintype "passive"))
    )
    (net (code "85") (name "unconnected-(P17-Pad11)") (class "Default")
      (node (ref "P17") (pin "11") (pinfunction "11_11") (pintype "passive"))
    )
    (net (code "86") (name "unconnected-(P17-Pad12)") (class "Default")
      (node (ref "P17") (pin "12") (pinfunction "12_12") (pintype "passive"))
    )
    (net (code "87") (name "unconnected-(P17-Pad13)") (class "Default")
      (node (ref "P17") (pin "13") (pinfunction "13_13") (pintype "passive"))
    )
    (net (code "88") (name "unconnected-(P17-Pad15)") (class "Default")
      (node (ref "P17") (pin "15") (pinfunction "15_15") (pintype "passive"))
    )
    (net (code "89") (name "unconnected-(X1-R1_5-Pad4)") (class "Default")
      (node (ref "X1") (pin "4") (pinfunction "R1_5_4") (pintype "passive"))
    )
    (net (code "90") (name "unconnected-(X1-R1_6-Pad5)") (class "Default")
      (node (ref "X1") (pin "5") (pinfunction "R1_6_5") (pintype "passive"))
    )
    (net (code "91") (name "unconnected-(X1-R1_7-Pad6)") (class "Default")
      (node (ref "X1") (pin "6") (pinfunction "R1_7_6") (pintype "passive"))
    )
    (net (code "92") (name "unconnected-(X1-R2_5-Pad1)") (class "Default")
      (node (ref "X1") (pin "1") (pinfunction "R2_5_1") (pintype "passive"))
    )
    (net (code "93") (name "unconnected-(X1-R2_6-Pad2)") (class "Default")
      (node (ref "X1") (pin "2") (pinfunction "R2_6_2") (pintype "passive"))
    )
    (net (code "94") (name "unconnected-(X1-R2_7-Pad3)") (class "Default")
      (node (ref "X1") (pin "3") (pinfunction "R2_7_3") (pintype "passive"))
    )
    (net (code "95") (name "unconnected-(X2-R1_5-Pad4)") (class "Default")
      (node (ref "X2") (pin "4") (pinfunction "R1_5_4") (pintype "passive"))
    )
    (net (code "96") (name "unconnected-(X2-R1_6-Pad5)") (class "Default")
      (node (ref "X2") (pin "5") (pinfunction "R1_6_5") (pintype "passive"))
    )
    (net (code "97") (name "unconnected-(X2-R1_7-Pad6)") (class "Default")
      (node (ref "X2") (pin "6") (pinfunction "R1_7_6") (pintype "passive"))
    )
    (net (code "98") (name "unconnected-(X2-R2_5-Pad1)") (class "Default")
      (node (ref "X2") (pin "1") (pinfunction "R2_5_1") (pintype "passive"))
    )
    (net (code "99") (name "unconnected-(X2-R2_6-Pad2)") (class "Default")
      (node (ref "X2") (pin "2") (pinfunction "R2_6_2") (pintype "passive"))
    )
    (net (code "100") (name "unconnected-(X2-R2_7-Pad3)") (class "Default")
      (node (ref "X2") (pin "3") (pinfunction "R2_7_3") (pintype "passive"))
    )
    (net (code "101") (name "unconnected-(X3-R1_5-Pad4)") (class "Default")
      (node (ref "X3") (pin "4") (pinfunction "R1_5_4") (pintype "passive"))
    )
    (net (code "102") (name "unconnected-(X3-R1_6-Pad5)") (class "Default")
      (node (ref "X3") (pin "5") (pinfunction "R1_6_5") (pintype "passive"))
    )
    (net (code "103") (name "unconnected-(X3-R1_7-Pad6)") (class "Default")
      (node (ref "X3") (pin "6") (pinfunction "R1_7_6") (pintype "passive"))
    )
    (net (code "104") (name "unconnected-(X3-R2_5-Pad1)") (class "Default")
      (node (ref "X3") (pin "1") (pinfunction "R2_5_1") (pintype "passive"))
    )
    (net (code "105") (name "unconnected-(X3-R2_6-Pad2)") (class "Default")
      (node (ref "X3") (pin "2") (pinfunction "R2_6_2") (pintype "passive"))
    )
    (net (code "106") (name "unconnected-(X3-R2_7-Pad3)") (class "Default")
      (node (ref "X3") (pin "3") (pinfunction "R2_7_3") (pintype "passive"))
    )
    (net (code "107") (name "unconnected-(X4-R1_5-Pad4)") (class "Default")
      (node (ref "X4") (pin "4") (pinfunction "R1_5_4") (pintype "passive"))
    )
    (net (code "108") (name "unconnected-(X4-R1_6-Pad5)") (class "Default")
      (node (ref "X4") (pin "5") (pinfunction "R1_6_5") (pintype "passive"))
    )
    (net (code "109") (name "unconnected-(X4-R1_7-Pad6)") (class "Default")
      (node (ref "X4") (pin "6") (pinfunction "R1_7_6") (pintype "passive"))
    )
    (net (code "110") (name "unconnected-(X4-R2_5-Pad1)") (class "Default")
      (node (ref "X4") (pin "1") (pinfunction "R2_5_1") (pintype "passive"))
    )
    (net (code "111") (name "unconnected-(X4-R2_6-Pad2)") (class "Default")
      (node (ref "X4") (pin "2") (pinfunction "R2_6_2") (pintype "passive"))
    )
    (net (code "112") (name "unconnected-(X4-R2_7-Pad3)") (class "Default")
      (node (ref "X4") (pin "3") (pinfunction "R2_7_3") (pintype "passive"))
    )
    (net (code "113") (name "unconnected-(X5-R1_5-Pad4)") (class "Default")
      (node (ref "X5") (pin "4") (pinfunction "R1_5_4") (pintype "passive"))
    )
    (net (code "114") (name "unconnected-(X5-R1_6-Pad5)") (class "Default")
      (node (ref "X5") (pin "5") (pinfunction "R1_6_5") (pintype "passive"))
    )
    (net (code "115") (name "unconnected-(X5-R1_7-Pad6)") (class "Default")
      (node (ref "X5") (pin "6") (pinfunction "R1_7_6") (pintype "passive"))
    )
    (net (code "116") (name "unconnected-(X5-R2_5-Pad1)") (class "Default")
      (node (ref "X5") (pin "1") (pinfunction "R2_5_1") (pintype "passive"))
    )
    (net (code "117") (name "unconnected-(X5-R2_6-Pad2)") (class "Default")
      (node (ref "X5") (pin "2") (pinfunction "R2_6_2") (pintype "passive"))
    )
    (net (code "118") (name "unconnected-(X5-R2_7-Pad3)") (class "Default")
      (node (ref "X5") (pin "3") (pinfunction "R2_7_3") (pintype "passive"))
    )
    (net (code "119") (name "unconnected-(X6-R1_5-Pad4)") (class "Default")
      (node (ref "X6") (pin "4") (pinfunction "R1_5_4") (pintype "passive"))
    )
    (net (code "120") (name "unconnected-(X6-R1_6-Pad5)") (class "Default")
      (node (ref "X6") (pin "5") (pinfunction "R1_6_5") (pintype "passive"))
    )
    (net (code "121") (name "unconnected-(X6-R1_7-Pad6)") (class "Default")
      (node (ref "X6") (pin "6") (pinfunction "R1_7_6") (pintype "passive"))
    )
    (net (code "122") (name "unconnected-(X6-R2_5-Pad1)") (class "Default")
      (node (ref "X6") (pin "1") (pinfunction "R2_5_1") (pintype "passive"))
    )
    (net (code "123") (name "unconnected-(X6-R2_6-Pad2)") (class "Default")
      (node (ref "X6") (pin "2") (pinfunction "R2_6_2") (pintype "passive"))
    )
    (net (code "124") (name "unconnected-(X6-R2_7-Pad3)") (class "Default")
      (node (ref "X6") (pin "3") (pinfunction "R2_7_3") (pintype "passive"))
    )
    (net (code "125") (name "unconnected-(X7-R1_5-Pad4)") (class "Default")
      (node (ref "X7") (pin "4") (pinfunction "R1_5_4") (pintype "passive"))
    )
    (net (code "126") (name "unconnected-(X7-R1_6-Pad5)") (class "Default")
      (node (ref "X7") (pin "5") (pinfunction "R1_6_5") (pintype "passive"))
    )
    (net (code "127") (name "unconnected-(X7-R1_7-Pad6)") (class "Default")
      (node (ref "X7") (pin "6") (pinfunction "R1_7_6") (pintype "passive"))
    )
    (net (code "128") (name "unconnected-(X7-R2_5-Pad1)") (class "Default")
      (node (ref "X7") (pin "1") (pinfunction "R2_5_1") (pintype "passive"))
    )
    (net (code "129") (name "unconnected-(X7-R2_6-Pad2)") (class "Default")
      (node (ref "X7") (pin "2") (pinfunction "R2_6_2") (pintype "passive"))
    )
    (net (code "130") (name "unconnected-(X7-R2_7-Pad3)") (class "Default")
      (node (ref "X7") (pin "3") (pinfunction "R2_7_3") (pintype "passive"))
    )
    (net (code "131") (name "unconnected-(X8-R2_5-Pad1)") (class "Default")
      (node (ref "X8") (pin "1") (pinfunction "R2_5_1") (pintype "passive"))
    )
    (net (code "132") (name "unconnected-(X8-R2_6-Pad2)") (class "Default")
      (node (ref "X8") (pin "2") (pinfunction "R2_6_2") (pintype "passive"))
    )
    (net (code "133") (name "unconnected-(X8-R2_7-Pad3)") (class "Default")
      (node (ref "X8") (pin "3") (pinfunction "R2_7_3") (pintype "passive"))
    )
    (net (code "134") (name "unconnected-(X9-+V-Pad3)") (class "Default")
      (node (ref "X9") (pin "3") (pinfunction "+V_3") (pintype "passive"))
    )
    (net (code "135") (name "unconnected-(X9--V-Pad4)") (class "Default")
      (node (ref "X9") (pin "4") (pinfunction "-V_4") (pintype "passive"))
    )
  )
)
